# busboard.net
KiCad netlist of a schematic drawn in EAGLE
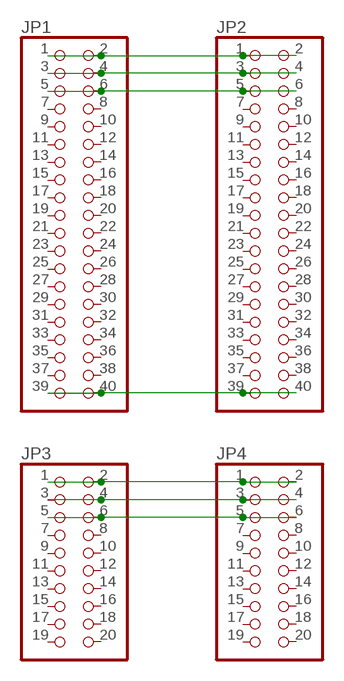
[diagram p0: schematic, sheet 1]

(export (version "E")
  (design (tool "Eeschema 10.0.6"))
  (components
    (comp (ref "JP1")
      (value "PINHD-2X20")
      (footprint "eagle-import:2X20")
      (libsource (lib "eagle-import") (part "PINHD-2X20"))
    )
    (comp (ref "JP2")
      (value "PINHD-2X20")
      (footprint "eagle-import:2X20")
      (libsource (lib "eagle-import") (part "PINHD-2X20"))
    )
    (comp (ref "JP3")
      (value "PINHD-2X10")
      (footprint "eagle-import:2X10")
      (libsource (lib "eagle-import") (part "PINHD-2X10"))
    )
    (comp (ref "JP4")
      (value "PINHD-2X10")
      (footprint "eagle-import:2X10")
      (libsource (lib "eagle-import") (part "PINHD-2X10"))
    )
  )
  (nets
    (net (code "1") (name "Net-(JP1-Pad1)") (class "Default")
      (node (ref "JP1") (pin "1") (pinfunction "1_1") (pintype "passive"))
      (node (ref "JP1") (pin "2") (pinfunction "2_2") (pintype "passive"))
      (node (ref "JP2") (pin "1") (pinfunction "1_1") (pintype "passive"))
      (node (ref "JP2") (pin "2") (pinfunction "2_2") (pintype "passive"))
    )
    (net (code "2") (name "Net-(JP1-Pad3)") (class "Default")
      (node (ref "JP1") (pin "3") (pinfunction "3_3") (pintype "passive"))
      (node (ref "JP1") (pin "4") (pinfunction "4_4") (pintype "passive"))
      (node (ref "JP2") (pin "3") (pinfunction "3_3") (pintype "passive"))
      (node (ref "JP2") (pin "4") (pinfunction "4_4") (pintype "passive"))
    )
    (net (code "3") (name "Net-(JP1-Pad5)") (class "Default")
      (node (ref "JP1") (pin "5") (pinfunction "5_5") (pintype "passive"))
      (node (ref "JP1") (pin "6") (pinfunction "6_6") (pintype "passive"))
      (node (ref "JP2") (pin "5") (pinfunction "5_5") (pintype "passive"))
      (node (ref "JP2") (pin "6") (pinfunction "6_6") (pintype "passive"))
    )
    (net (code "4") (name "Net-(JP1-Pad39)") (class "Default")
      (node (ref "JP1") (pin "39") (pinfunction "39_39") (pintype "passive"))
      (node (ref "JP1") (pin "40") (pinfunction "40_40") (pintype "passive"))
      (node (ref "JP2") (pin "39") (pinfunction "39_39") (pintype "passive"))
      (node (ref "JP2") (pin "40") (pinfunction "40_40") (pintype "passive"))
    )
    (net (code "5") (name "Net-(JP3-Pad1)") (class "Default")
      (node (ref "JP3") (pin "1") (pinfunction "1_1") (pintype "passive"))
      (node (ref "JP3") (pin "2") (pinfunction "2_2") (pintype "passive"))
      (node (ref "JP4") (pin "1") (pinfunction "1_1") (pintype "passive"))
      (node (ref "JP4") (pin "2") (pinfunction "2_2") (pintype "passive"))
    )
    (net (code "6") (name "Net-(JP3-Pad3)") (class "Default")
      (node (ref "JP3") (pin "3") (pinfunction "3_3") (pintype "passive"))
      (node (ref "JP3") (pin "4") (pinfunction "4_4") (pintype "passive"))
      (node (ref "JP4") (pin "3") (pinfunction "3_3") (pintype "passive"))
      (node (ref "JP4") (pin "4") (pinfunction "4_4") (pintype "passive"))
    )
    (net (code "7") (name "Net-(JP3-Pad5)") (class "Default")
      (node (ref "JP3") (pin "5") (pinfunction "5_5") (pintype "passive"))
      (node (ref "JP3") (pin "6") (pinfunction "6_6") (pintype "passive"))
      (node (ref "JP4") (pin "5") (pinfunction "5_5") (pintype "passive"))
      (node (ref "JP4") (pin "6") (pinfunction "6_6") (pintype "passive"))
    )
    (net (code "8") (name "unconnected-(JP1-Pad7)") (class "Default")
      (node (ref "JP1") (pin "7") (pinfunction "7_7") (pintype "passive"))
    )
    (net (code "9") (name "unconnected-(JP1-Pad8)") (class "Default")
      (node (ref "JP1") (pin "8") (pinfunction "8_8") (pintype "passive"))
    )
    (net (code "10") (name "unconnected-(JP1-Pad9)") (class "Default")
      (node (ref "JP1") (pin "9") (pinfunction "9_9") (pintype "passive"))
    )
    (net (code "11") (name "unconnected-(JP1-Pad10)") (class "Default")
      (node (ref "JP1") (pin "10") (pinfunction "10_10") (pintype "passive"))
    )
    (net (code "12") (name "unconnected-(JP1-Pad11)") (class "Default")
      (node (ref "JP1") (pin "11") (pinfunction "11_11") (pintype "passive"))
    )
    (net (code "13") (name "unconnected-(JP1-Pad12)") (class "Default")
      (node (ref "JP1") (pin "12") (pinfunction "12_12") (pintype "passive"))
    )
    (net (code "14") (name "unconnected-(JP1-Pad13)") (class "Default")
      (node (ref "JP1") (pin "13") (pinfunction "13_13") (pintype "passive"))
    )
    (net (code "15") (name "unconnected-(JP1-Pad14)") (class "Default")
      (node (ref "JP1") (pin "14") (pinfunction "14_14") (pintype "passive"))
    )
    (net (code "16") (name "unconnected-(JP1-Pad15)") (class "Default")
      (node (ref "JP1") (pin "15") (pinfunction "15_15") (pintype "passive"))
    )
    (net (code "17") (name "unconnected-(JP1-Pad16)") (class "Default")
      (node (ref "JP1") (pin "16") (pinfunction "16_16") (pintype "passive"))
    )
    (net (code "18") (name "unconnected-(JP1-Pad17)") (class "Default")
      (node (ref "JP1") (pin "17") (pinfunction "17_17") (pintype "passive"))
    )
    (net (code "19") (name "unconnected-(JP1-Pad18)") (class "Default")
      (node (ref "JP1") (pin "18") (pinfunction "18_18") (pintype "passive"))
    )
    (net (code "20") (name "unconnected-(JP1-Pad19)") (class "Default")
      (node (ref "JP1") (pin "19") (pinfunction "19_19") (pintype "passive"))
    )
    (net (code "21") (name "unconnected-(JP1-Pad20)") (class "Default")
      (node (ref "JP1") (pin "20") (pinfunction "20_20") (pintype "passive"))
    )
    (net (code "22") (name "unconnected-(JP1-Pad21)") (class "Default")
      (node (ref "JP1") (pin "21") (pinfunction "21_21") (pintype "passive"))
    )
    (net (code "23") (name "unconnected-(JP1-Pad22)") (class "Default")
      (node (ref "JP1") (pin "22") (pinfunction "22_22") (pintype "passive"))
    )
    (net (code "24") (name "unconnected-(JP1-Pad23)") (class "Default")
      (node (ref "JP1") (pin "23") (pinfunction "23_23") (pintype "passive"))
    )
    (net (code "25") (name "unconnected-(JP1-Pad24)") (class "Default")
      (node (ref "JP1") (pin "24") (pinfunction "24_24") (pintype "passive"))
    )
    (net (code "26") (name "unconnected-(JP1-Pad25)") (class "Default")
      (node (ref "JP1") (pin "25") (pinfunction "25_25") (pintype "passive"))
    )
    (net (code "27") (name "unconnected-(JP1-Pad26)") (class "Default")
      (node (ref "JP1") (pin "26") (pinfunction "26_26") (pintype "passive"))
    )
    (net (code "28") (name "unconnected-(JP1-Pad27)") (class "Default")
      (node (ref "JP1") (pin "27") (pinfunction "27_27") (pintype "passive"))
    )
    (net (code "29") (name "unconnected-(JP1-Pad28)") (class "Default")
      (node (ref "JP1") (pin "28") (pinfunction "28_28") (pintype "passive"))
    )
    (net (code "30") (name "unconnected-(JP1-Pad29)") (class "Default")
      (node (ref "JP1") (pin "29") (pinfunction "29_29") (pintype "passive"))
    )
    (net (code "31") (name "unconnected-(JP1-Pad30)") (class "Default")
      (node (ref "JP1") (pin "30") (pinfunction "30_30") (pintype "passive"))
    )
    (net (code "32") (name "unconnected-(JP1-Pad31)") (class "Default")
      (node (ref "JP1") (pin "31") (pinfunction "31_31") (pintype "passive"))
    )
    (net (code "33") (name "unconnected-(JP1-Pad32)") (class "Default")
      (node (ref "JP1") (pin "32") (pinfunction "32_32") (pintype "passive"))
    )
    (net (code "34") (name "unconnected-(JP1-Pad33)") (class "Default")
      (node (ref "JP1") (pin "33") (pinfunction "33_33") (pintype "passive"))
    )
    (net (code "35") (name "unconnected-(JP1-Pad34)") (class "Default")
      (node (ref "JP1") (pin "34") (pinfunction "34_34") (pintype "passive"))
    )
    (net (code "36") (name "unconnected-(JP1-Pad35)") (class "Default")
      (node (ref "JP1") (pin "35") (pinfunction "35_35") (pintype "passive"))
    )
    (net (code "37") (name "unconnected-(JP1-Pad36)") (class "Default")
      (node (ref "JP1") (pin "36") (pinfunction "36_36") (pintype "passive"))
    )
    (net (code "38") (name "unconnected-(JP1-Pad37)") (class "Default")
      (node (ref "JP1") (pin "37") (pinfunction "37_37") (pintype "passive"))
    )
    (net (code "39") (name "unconnected-(JP1-Pad38)") (class "Default")
      (node (ref "JP1") (pin "38") (pinfunction "38_38") (pintype "passive"))
    )
    (net (code "40") (name "unconnected-(JP2-Pad7)") (class "Default")
      (node (ref "JP2") (pin "7") (pinfunction "7_7") (pintype "passive"))
    )
    (net (code "41") (name "unconnected-(JP2-Pad8)") (class "Default")
      (node (ref "JP2") (pin "8") (pinfunction "8_8") (pintype "passive"))
    )
    (net (code "42") (name "unconnected-(JP2-Pad9)") (class "Default")
      (node (ref "JP2") (pin "9") (pinfunction "9_9") (pintype "passive"))
    )
    (net (code "43") (name "unconnected-(JP2-Pad10)") (class "Default")
      (node (ref "JP2") (pin "10") (pinfunction "10_10") (pintype "passive"))
    )
    (net (code "44") (name "unconnected-(JP2-Pad11)") (class "Default")
      (node (ref "JP2") (pin "11") (pinfunction "11_11") (pintype "passive"))
    )
    (net (code "45") (name "unconnected-(JP2-Pad12)") (class "Default")
      (node (ref "JP2") (pin "12") (pinfunction "12_12") (pintype "passive"))
    )
    (net (code "46") (name "unconnected-(JP2-Pad13)") (class "Default")
      (node (ref "JP2") (pin "13") (pinfunction "13_13") (pintype "passive"))
    )
    (net (code "47") (name "unconnected-(JP2-Pad14)") (class "Default")
      (node (ref "JP2") (pin "14") (pinfunction "14_14") (pintype "passive"))
    )
    (net (code "48") (name "unconnected-(JP2-Pad15)") (class "Default")
      (node (ref "JP2") (pin "15") (pinfunction "15_15") (pintype "passive"))
    )
    (net (code "49") (name "unconnected-(JP2-Pad16)") (class "Default")
      (node (ref "JP2") (pin "16") (pinfunction "16_16") (pintype "passive"))
    )
    (net (code "50") (name "unconnected-(JP2-Pad17)") (class "Default")
      (node (ref "JP2") (pin "17") (pinfunction "17_17") (pintype "passive"))
    )
    (net (code "51") (name "unconnected-(JP2-Pad18)") (class "Default")
      (node (ref "JP2") (pin "18") (pinfunction "18_18") (pintype "passive"))
    )
    (net (code "52") (name "unconnected-(JP2-Pad19)") (class "Default")
      (node (ref "JP2") (pin "19") (pinfunction "19_19") (pintype "passive"))
    )
    (net (code "53") (name "unconnected-(JP2-Pad20)") (class "Default")
      (node (ref "JP2") (pin "20") (pinfunction "20_20") (pintype "passive"))
    )
    (net (code "54") (name "unconnected-(JP2-Pad21)") (class "Default")
      (node (ref "JP2") (pin "21") (pinfunction "21_21") (pintype "passive"))
    )
    (net (code "55") (name "unconnected-(JP2-Pad22)") (class "Default")
      (node (ref "JP2") (pin "22") (pinfunction "22_22") (pintype "passive"))
    )
    (net (code "56") (name "unconnected-(JP2-Pad23)") (class "Default")
      (node (ref "JP2") (pin "23") (pinfunction "23_23") (pintype "passive"))
    )
    (net (code "57") (name "unconnected-(JP2-Pad24)") (class "Default")
      (node (ref "JP2") (pin "24") (pinfunction "24_24") (pintype "passive"))
    )
    (net (code "58") (name "unconnected-(JP2-Pad25)") (class "Default")
      (node (ref "JP2") (pin "25") (pinfunction "25_25") (pintype "passive"))
    )
    (net (code "59") (name "unconnected-(JP2-Pad26)") (class "Default")
      (node (ref "JP2") (pin "26") (pinfunction "26_26") (pintype "passive"))
    )
    (net (code "60") (name "unconnected-(JP2-Pad27)") (class "Default")
      (node (ref "JP2") (pin "27") (pinfunction "27_27") (pintype "passive"))
    )
    (net (code "61") (name "unconnected-(JP2-Pad28)") (class "Default")
      (node (ref "JP2") (pin "28") (pinfunction "28_28") (pintype "passive"))
    )
    (net (code "62") (name "unconnected-(JP2-Pad29)") (class "Default")
      (node (ref "JP2") (pin "29") (pinfunction "29_29") (pintype "passive"))
    )
    (net (code "63") (name "unconnected-(JP2-Pad30)") (class "Default")
      (node (ref "JP2") (pin "30") (pinfunction "30_30") (pintype "passive"))
    )
    (net (code "64") (name "unconnected-(JP2-Pad31)") (class "Default")
      (node (ref "JP2") (pin "31") (pinfunction "31_31") (pintype "passive"))
    )
    (net (code "65") (name "unconnected-(JP2-Pad32)") (class "Default")
      (node (ref "JP2") (pin "32") (pinfunction "32_32") (pintype "passive"))
    )
    (net (code "66") (name "unconnected-(JP2-Pad33)") (class "Default")
      (node (ref "JP2") (pin "33") (pinfunction "33_33") (pintype "passive"))
    )
    (net (code "67") (name "unconnected-(JP2-Pad34)") (class "Default")
      (node (ref "JP2") (pin "34") (pinfunction "34_34") (pintype "passive"))
    )
    (net (code "68") (name "unconnected-(JP2-Pad35)") (class "Default")
      (node (ref "JP2") (pin "35") (pinfunction "35_35") (pintype "passive"))
    )
    (net (code "69") (name "unconnected-(JP2-Pad36)") (class "Default")
      (node (ref "JP2") (pin "36") (pinfunction "36_36") (pintype "passive"))
    )
    (net (code "70") (name "unconnected-(JP2-Pad37)") (class "Default")
      (node (ref "JP2") (pin "37") (pinfunction "37_37") (pintype "passive"))
    )
    (net (code "71") (name "unconnected-(JP2-Pad38)") (class "Default")
      (node (ref "JP2") (pin "38") (pinfunction "38_38") (pintype "passive"))
    )
    (net (code "72") (name "unconnected-(JP3-Pad7)") (class "Default")
      (node (ref "JP3") (pin "7") (pinfunction "7_7") (pintype "passive"))
    )
    (net (code "73") (name "unconnected-(JP3-Pad8)") (class "Default")
      (node (ref "JP3") (pin "8") (pinfunction "8_8") (pintype "passive"))
    )
    (net (code "74") (name "unconnected-(JP3-Pad9)") (class "Default")
      (node (ref "JP3") (pin "9") (pinfunction "9_9") (pintype "passive"))
    )
    (net (code "75") (name "unconnected-(JP3-Pad10)") (class "Default")
      (node (ref "JP3") (pin "10") (pinfunction "10_10") (pintype "passive"))
    )
    (net (code "76") (name "unconnected-(JP3-Pad11)") (class "Default")
      (node (ref "JP3") (pin "11") (pinfunction "11_11") (pintype "passive"))
    )
    (net (code "77") (name "unconnected-(JP3-Pad12)") (class "Default")
      (node (ref "JP3") (pin "12") (pinfunction "12_12") (pintype "passive"))
    )
    (net (code "78") (name "unconnected-(JP3-Pad13)") (class "Default")
      (node (ref "JP3") (pin "13") (pinfunction "13_13") (pintype "passive"))
    )
    (net (code "79") (name "unconnected-(JP3-Pad14)") (class "Default")
      (node (ref "JP3") (pin "14") (pinfunction "14_14") (pintype "passive"))
    )
    (net (code "80") (name "unconnected-(JP3-Pad15)") (class "Default")
      (node (ref "JP3") (pin "15") (pinfunction "15_15") (pintype "passive"))
    )
    (net (code "81") (name "unconnected-(JP3-Pad16)") (class "Default")
      (node (ref "JP3") (pin "16") (pinfunction "16_16") (pintype "passive"))
    )
    (net (code "82") (name "unconnected-(JP3-Pad17)") (class "Default")
      (node (ref "JP3") (pin "17") (pinfunction "17_17") (pintype "passive"))
    )
    (net (code "83") (name "unconnected-(JP3-Pad18)") (class "Default")
      (node (ref "JP3") (pin "18") (pinfunction "18_18") (pintype "passive"))
    )
    (net (code "84") (name "unconnected-(JP3-Pad19)") (class "Default")
      (node (ref "JP3") (pin "19") (pinfunction "19_19") (pintype "passive"))
    )
    (net (code "85") (name "unconnected-(JP3-Pad20)") (class "Default")
      (node (ref "JP3") (pin "20") (pinfunction "20_20") (pintype "passive"))
    )
    (net (code "86") (name "unconnected-(JP4-Pad7)") (class "Default")
      (node (ref "JP4") (pin "7") (pinfunction "7_7") (pintype "passive"))
    )
    (net (code "87") (name "unconnected-(JP4-Pad8)") (class "Default")
      (node (ref "JP4") (pin "8") (pinfunction "8_8") (pintype "passive"))
    )
    (net (code "88") (name "unconnected-(JP4-Pad9)") (class "Default")
      (node (ref "JP4") (pin "9") (pinfunction "9_9") (pintype "passive"))
    )
    (net (code "89") (name "unconnected-(JP4-Pad10)") (class "Default")
      (node (ref "JP4") (pin "10") (pinfunction "10_10") (pintype "passive"))
    )
    (net (code "90") (name "unconnected-(JP4-Pad11)") (class "Default")
      (node (ref "JP4") (pin "11") (pinfunction "11_11") (pintype "passive"))
    )
    (net (code "91") (name "unconnected-(JP4-Pad12)") (class "Default")
      (node (ref "JP4") (pin "12") (pinfunction "12_12") (pintype "passive"))
    )
    (net (code "92") (name "unconnected-(JP4-Pad13)") (class "Default")
      (node (ref "JP4") (pin "13") (pinfunction "13_13") (pintype "passive"))
    )
    (net (code "93") (name "unconnected-(JP4-Pad14)") (class "Default")
      (node (ref "JP4") (pin "14") (pinfunction "14_14") (pintype "passive"))
    )
    (net (code "94") (name "unconnected-(JP4-Pad15)") (class "Default")
      (node (ref "JP4") (pin "15") (pinfunction "15_15") (pintype "passive"))
    )
    (net (code "95") (name "unconnected-(JP4-Pad16)") (class "Default")
      (node (ref "JP4") (pin "16") (pinfunction "16_16") (pintype "passive"))
    )
    (net (code "96") (name "unconnected-(JP4-Pad17)") (class "Default")
      (node (ref "JP4") (pin "17") (pinfunction "17_17") (pintype "passive"))
    )
    (net (code "97") (name "unconnected-(JP4-Pad18)") (class "Default")
      (node (ref "JP4") (pin "18") (pinfunction "18_18") (pintype "passive"))
    )
    (net (code "98") (name "unconnected-(JP4-Pad19)") (class "Default")
      (node (ref "JP4") (pin "19") (pinfunction "19_19") (pintype "passive"))
    )
    (net (code "99") (name "unconnected-(JP4-Pad20)") (class "Default")
      (node (ref "JP4") (pin "20") (pinfunction "20_20") (pintype "passive"))
    )
  )
)
